# Xbeetrans.net
KiCad netlist of a schematic drawn in EAGLE
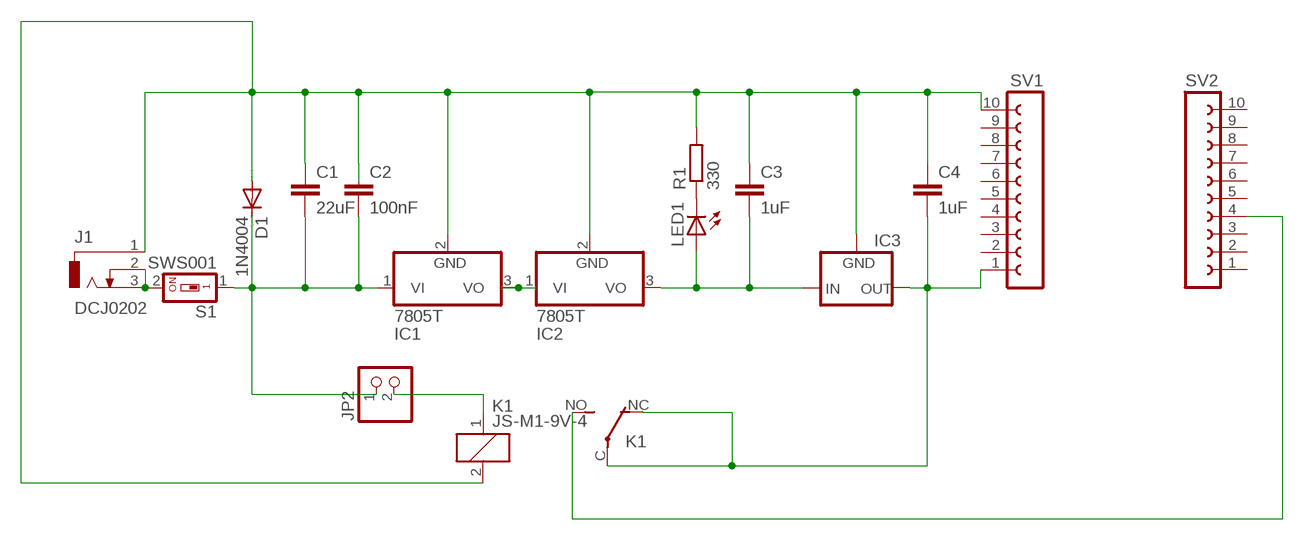
[diagram p0: schematic, sheet 1]

(export (version "E")
  (design (tool "Eeschema 10.0.6"))
  (components
    (comp (ref "C1")
      (value "22uF")
      (footprint "eagle-import:C025-025X050")
      (libsource (lib "eagle-import") (part "C-EU025-025X050"))
    )
    (comp (ref "C2")
      (value "100nF")
      (footprint "eagle-import:C025-025X050")
      (libsource (lib "eagle-import") (part "C-EU025-025X050"))
    )
    (comp (ref "C3")
      (value "1uF")
      (footprint "eagle-import:C025-025X050")
      (libsource (lib "eagle-import") (part "C-EU025-025X050"))
    )
    (comp (ref "C4")
      (value "1uF")
      (footprint "eagle-import:C025-025X050")
      (libsource (lib "eagle-import") (part "C-EU025-025X050"))
    )
    (comp (ref "D1")
      (value "1N4004")
      (footprint "eagle-import:DO41-10")
      (libsource (lib "eagle-import") (part "1N4004"))
    )
    (comp (ref "IC1")
      (value "7805T")
      (footprint "eagle-import:TO220H")
      (libsource (lib "eagle-import") (part "78T05"))
    )
    (comp (ref "IC2")
      (value "7805T")
      (footprint "eagle-import:TO220H")
      (libsource (lib "eagle-import") (part "78T05"))
    )
    (comp (ref "IC3")
      (value "MCP1700TRI")
      (footprint "eagle-import:TO92")
      (libsource (lib "eagle-import") (part "MCP1700TRI"))
    )
    (comp (ref "J1")
      (value "DCJ0202")
      (footprint "eagle-import:DCJ0202")
      (libsource (lib "eagle-import") (part "DCJ0202"))
    )
    (comp (ref "JP2")
      (value "PINHD-1X2")
      (footprint "eagle-import:1X02")
      (libsource (lib "eagle-import") (part "PINHD-1X2"))
    )
    (comp (ref "K1")
      (value "JS-M1-9V-4")
      (footprint "eagle-import:JS-M")
      (libsource (lib "eagle-import") (part "JS-M1-9V-4"))
    )
    (comp (ref "LED1")
      (value "LED3MM")
      (footprint "eagle-import:LED3MM")
      (libsource (lib "eagle-import") (part "LED3MM"))
    )
    (comp (ref "R1")
      (value "330")
      (footprint "eagle-import:0204_5")
      (libsource (lib "eagle-import") (part "R-EU_0204/5"))
    )
    (comp (ref "S1")
      (value "SWS001")
      (footprint "eagle-import:SMS-001")
      (libsource (lib "eagle-import") (part "SWS001"))
    )
    (comp (ref "SV1")
      (value "FE10-1")
      (footprint "eagle-import:FE10")
      (libsource (lib "eagle-import") (part "FE10-1"))
    )
    (comp (ref "SV2")
      (value "FE10-1")
      (footprint "eagle-import:FE10")
      (libsource (lib "eagle-import") (part "FE10-1"))
    )
  )
  (nets
    (net (code "1") (name "Net-(IC1-GND)") (class "Default")
      (node (ref "C1") (pin "1") (pinfunction "1_1") (pintype "passive"))
      (node (ref "C2") (pin "1") (pinfunction "1_1") (pintype "passive"))
      (node (ref "C3") (pin "1") (pinfunction "1_1") (pintype "passive"))
      (node (ref "C4") (pin "1") (pinfunction "1_1") (pintype "passive"))
      (node (ref "D1") (pin "A") (pinfunction "A_A") (pintype "passive"))
      (node (ref "IC1") (pin "2") (pinfunction "GND_2") (pintype "passive"))
      (node (ref "IC2") (pin "2") (pinfunction "GND_2") (pintype "passive"))
      (node (ref "IC3") (pin "1") (pinfunction "GND_1") (pintype "input"))
      (node (ref "J1") (pin "1") (pinfunction "1_1") (pintype "passive"))
      (node (ref "K1") (pin "2") (pinfunction "2_2") (pintype "passive"))
      (node (ref "R1") (pin "2") (pinfunction "2_2") (pintype "passive"))
      (node (ref "SV1") (pin "10") (pinfunction "10_10") (pintype "passive"))
    )
    (net (code "2") (name "Net-(IC1-VI)") (class "Default")
      (node (ref "C1") (pin "2") (pinfunction "2_2") (pintype "passive"))
      (node (ref "C2") (pin "2") (pinfunction "2_2") (pintype "passive"))
      (node (ref "D1") (pin "C") (pinfunction "C_C") (pintype "passive"))
      (node (ref "IC1") (pin "1") (pinfunction "VI_1") (pintype "input"))
      (node (ref "JP2") (pin "1") (pinfunction "1_1") (pintype "passive"))
      (node (ref "S1") (pin "1") (pinfunction "1_1") (pintype "passive"))
    )
    (net (code "3") (name "Net-(IC1-VO)") (class "Default")
      (node (ref "IC1") (pin "3") (pinfunction "VO_3") (pintype "passive"))
      (node (ref "IC2") (pin "1") (pinfunction "VI_1") (pintype "input"))
    )
    (net (code "4") (name "Net-(IC2-VO)") (class "Default")
      (node (ref "C3") (pin "2") (pinfunction "2_2") (pintype "passive"))
      (node (ref "IC2") (pin "3") (pinfunction "VO_3") (pintype "passive"))
      (node (ref "IC3") (pin "2") (pinfunction "IN_2") (pintype "input"))
      (node (ref "LED1") (pin "A") (pinfunction "A_A") (pintype "passive"))
    )
    (net (code "5") (name "Net-(IC3-OUT)") (class "Default")
      (node (ref "C4") (pin "2") (pinfunction "2_2") (pintype "passive"))
      (node (ref "IC3") (pin "3") (pinfunction "OUT_3") (pintype "passive"))
      (node (ref "K1") (pin "C") (pinfunction "P_C") (pintype "passive"))
      (node (ref "K1") (pin "NC") (pinfunction "O_NC") (pintype "passive"))
      (node (ref "SV1") (pin "1") (pinfunction "1_1") (pintype "passive"))
    )
    (net (code "6") (name "Net-(J1-Pad2)") (class "Default")
      (node (ref "J1") (pin "2") (pinfunction "2_2") (pintype "passive"))
      (node (ref "J1") (pin "3") (pinfunction "3_3") (pintype "passive"))
      (node (ref "S1") (pin "2") (pinfunction "2_2") (pintype "passive"))
    )
    (net (code "7") (name "Net-(JP2-Pad2)") (class "Default")
      (node (ref "JP2") (pin "2") (pinfunction "2_2") (pintype "passive"))
      (node (ref "K1") (pin "1") (pinfunction "1_1") (pintype "passive"))
    )
    (net (code "8") (name "Net-(K1B-S)") (class "Default")
      (node (ref "K1") (pin "NO") (pinfunction "S_NO") (pintype "passive"))
      (node (ref "SV2") (pin "4") (pinfunction "4_4") (pintype "passive"))
    )
    (net (code "9") (name "Net-(LED1-C)") (class "Default")
      (node (ref "LED1") (pin "K") (pinfunction "C_K") (pintype "passive"))
      (node (ref "R1") (pin "1") (pinfunction "1_1") (pintype "passive"))
    )
    (net (code "10") (name "unconnected-(SV1-Pad2)") (class "Default")
      (node (ref "SV1") (pin "2") (pinfunction "2_2") (pintype "passive"))
    )
    (net (code "11") (name "unconnected-(SV1-Pad3)") (class "Default")
      (node (ref "SV1") (pin "3") (pinfunction "3_3") (pintype "passive"))
    )
    (net (code "12") (name "unconnected-(SV1-Pad4)") (class "Default")
      (node (ref "SV1") (pin "4") (pinfunction "4_4") (pintype "passive"))
    )
    (net (code "13") (name "unconnected-(SV1-Pad5)") (class "Default")
      (node (ref "SV1") (pin "5") (pinfunction "5_5") (pintype "passive"))
    )
    (net (code "14") (name "unconnected-(SV1-Pad6)") (class "Default")
      (node (ref "SV1") (pin "6") (pinfunction "6_6") (pintype "passive"))
    )
    (net (code "15") (name "unconnected-(SV1-Pad7)") (class "Default")
      (node (ref "SV1") (pin "7") (pinfunction "7_7") (pintype "passive"))
    )
    (net (code "16") (name "unconnected-(SV1-Pad8)") (class "Default")
      (node (ref "SV1") (pin "8") (pinfunction "8_8") (pintype "passive"))
    )
    (net (code "17") (name "unconnected-(SV1-Pad9)") (class "Default")
      (node (ref "SV1") (pin "9") (pinfunction "9_9") (pintype "passive"))
    )
    (net (code "18") (name "unconnected-(SV2-Pad1)") (class "Default")
      (node (ref "SV2") (pin "1") (pinfunction "1_1") (pintype "passive"))
    )
    (net (code "19") (name "unconnected-(SV2-Pad2)") (class "Default")
      (node (ref "SV2") (pin "2") (pinfunction "2_2") (pintype "passive"))
    )
    (net (code "20") (name "unconnected-(SV2-Pad3)") (class "Default")
      (node (ref "SV2") (pin "3") (pinfunction "3_3") (pintype "passive"))
    )
    (net (code "21") (name "unconnected-(SV2-Pad5)") (class "Default")
      (node (ref "SV2") (pin "5") (pinfunction "5_5") (pintype "passive"))
    )
    (net (code "22") (name "unconnected-(SV2-Pad6)") (class "Default")
      (node (ref "SV2") (pin "6") (pinfunction "6_6") (pintype "passive"))
    )
    (net (code "23") (name "unconnected-(SV2-Pad7)") (class "Default")
      (node (ref "SV2") (pin "7") (pinfunction "7_7") (pintype "passive"))
    )
    (net (code "24") (name "unconnected-(SV2-Pad8)") (class "Default")
      (node (ref "SV2") (pin "8") (pinfunction "8_8") (pintype "passive"))
    )
    (net (code "25") (name "unconnected-(SV2-Pad9)") (class "Default")
      (node (ref "SV2") (pin "9") (pinfunction "9_9") (pintype "passive"))
    )
    (net (code "26") (name "unconnected-(SV2-Pad10)") (class "Default")
      (node (ref "SV2") (pin "10") (pinfunction "10_10") (pintype "passive"))
    )
  )
)
